# mixer.net
KiCad netlist of a schematic drawn in Altium Designer
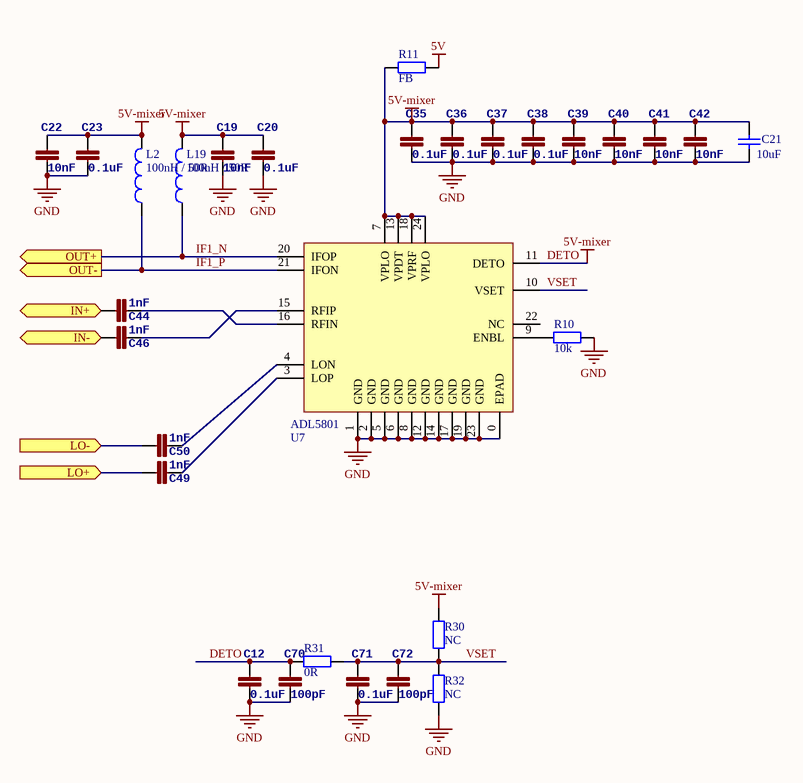
[diagram p0: mixer.SchDoc]

(export (version "E")
  (design (tool "Eeschema 10.0.6"))
  (components
    (comp (ref "C12")
      (value "0.1uF")
      (footprint "0402")
      (description "<b>Capacitor</b>\nStandard 0603 ceramic capacitor, and 0.1\" leaded capacitor.")
      (fields (field (name "PARTNO") "CC0402ZRY5V7BB104"))
      (libsource (lib "*") (part "CAP0402-CAP"))
    )
    (comp (ref "C19")
      (value "10nF")
      (footprint "0402")
      (description "<b>Capacitor</b>\nStandard 0603 ceramic capacitor, and 0.1\" leaded capacitor.")
      (fields (field (name "PARTNO") "CC0402ZRY5V7BB104"))
      (libsource (lib "*") (part "CAP0402-CAP"))
    )
    (comp (ref "C20")
      (value "0.1uF")
      (footprint "0402")
      (description "<b>Capacitor</b>\nStandard 0603 ceramic capacitor, and 0.1\" leaded capacitor.")
      (fields (field (name "PARTNO") "CC0402ZRY5V7BB104"))
      (libsource (lib "*") (part "CAP0402-CAP"))
    )
    (comp (ref "C21")
      (value "10uF")
      (footprint "0805")
      (description "Capacitor")
      (fields (field (name "PUBLISHER") "Altium Limited"))
      (libsource (lib "RTC6705") (part "Cap"))
    )
    (comp (ref "C22")
      (value "10nF")
      (footprint "0402")
      (description "<b>Capacitor</b>\nStandard 0603 ceramic capacitor, and 0.1\" leaded capacitor.")
      (fields (field (name "PARTNO") "CC0402ZRY5V7BB104"))
      (libsource (lib "*") (part "CAP0402-CAP"))
    )
    (comp (ref "C23")
      (value "0.1uF")
      (footprint "0402")
      (description "<b>Capacitor</b>\nStandard 0603 ceramic capacitor, and 0.1\" leaded capacitor.")
      (fields (field (name "PARTNO") "CC0402ZRY5V7BB104"))
      (libsource (lib "*") (part "CAP0402-CAP"))
    )
    (comp (ref "C35")
      (value "0.1uF")
      (footprint "0402")
      (description "<b>Capacitor</b>\nStandard 0603 ceramic capacitor, and 0.1\" leaded capacitor.")
      (fields (field (name "PARTNO") "CC0402ZRY5V7BB104"))
      (libsource (lib "*") (part "CAP0402-CAP"))
    )
    (comp (ref "C36")
      (value "0.1uF")
      (footprint "0402")
      (description "<b>Capacitor</b>\nStandard 0603 ceramic capacitor, and 0.1\" leaded capacitor.")
      (fields (field (name "PARTNO") "CC0402ZRY5V7BB104"))
      (libsource (lib "*") (part "CAP0402-CAP"))
    )
    (comp (ref "C37")
      (value "0.1uF")
      (footprint "0402")
      (description "<b>Capacitor</b>\nStandard 0603 ceramic capacitor, and 0.1\" leaded capacitor.")
      (fields (field (name "PARTNO") "CC0402ZRY5V7BB104"))
      (libsource (lib "*") (part "CAP0402-CAP"))
    )
    (comp (ref "C38")
      (value "0.1uF")
      (footprint "0402")
      (description "<b>Capacitor</b>\nStandard 0603 ceramic capacitor, and 0.1\" leaded capacitor.")
      (fields (field (name "PARTNO") "CC0402ZRY5V7BB104"))
      (libsource (lib "*") (part "CAP0402-CAP"))
    )
    (comp (ref "C39")
      (value "10nF")
      (footprint "0402")
      (description "<b>Capacitor</b>\nStandard 0603 ceramic capacitor, and 0.1\" leaded capacitor.")
      (fields (field (name "PARTNO") "CC0402ZRY5V7BB104"))
      (libsource (lib "*") (part "CAP0402-CAP"))
    )
    (comp (ref "C40")
      (value "10nF")
      (footprint "0402")
      (description "<b>Capacitor</b>\nStandard 0603 ceramic capacitor, and 0.1\" leaded capacitor.")
      (fields (field (name "PARTNO") "CC0402ZRY5V7BB104"))
      (libsource (lib "*") (part "CAP0402-CAP"))
    )
    (comp (ref "C41")
      (value "10nF")
      (footprint "0402")
      (description "<b>Capacitor</b>\nStandard 0603 ceramic capacitor, and 0.1\" leaded capacitor.")
      (fields (field (name "PARTNO") "CC0402ZRY5V7BB104"))
      (libsource (lib "*") (part "CAP0402-CAP"))
    )
    (comp (ref "C42")
      (value "10nF")
      (footprint "0402")
      (description "<b>Capacitor</b>\nStandard 0603 ceramic capacitor, and 0.1\" leaded capacitor.")
      (fields (field (name "PARTNO") "CC0402ZRY5V7BB104"))
      (libsource (lib "*") (part "CAP0402-CAP"))
    )
    (comp (ref "C44")
      (value "1nF")
      (footprint "0402")
      (description "<b>Capacitor</b>\nStandard 0603 ceramic capacitor, and 0.1\" leaded capacitor.")
      (fields (field (name "PARTNO") "CC0402ZRY5V7BB104"))
      (libsource (lib "") (part "CAP0402-CAP_1"))
    )
    (comp (ref "C46")
      (value "1nF")
      (footprint "0402")
      (description "<b>Capacitor</b>\nStandard 0603 ceramic capacitor, and 0.1\" leaded capacitor.")
      (fields (field (name "PARTNO") "CC0402ZRY5V7BB104"))
      (libsource (lib "") (part "CAP0402-CAP_1"))
    )
    (comp (ref "C49")
      (value "1nF")
      (footprint "0402")
      (description "<b>Capacitor</b>\nStandard 0603 ceramic capacitor, and 0.1\" leaded capacitor.")
      (fields (field (name "PARTNO") "CC0402ZRY5V7BB104"))
      (libsource (lib "") (part "CAP0402-CAP_1"))
    )
    (comp (ref "C50")
      (value "1nF")
      (footprint "0402")
      (description "<b>Capacitor</b>\nStandard 0603 ceramic capacitor, and 0.1\" leaded capacitor.")
      (fields (field (name "PARTNO") "CC0402ZRY5V7BB104"))
      (libsource (lib "") (part "CAP0402-CAP_1"))
    )
    (comp (ref "C70")
      (value "100pF")
      (footprint "0402")
      (description "<b>Capacitor</b>\nStandard 0603 ceramic capacitor, and 0.1\" leaded capacitor.")
      (fields (field (name "PARTNO") "CC0402ZRY5V7BB104"))
      (libsource (lib "*") (part "CAP0402-CAP"))
    )
    (comp (ref "C71")
      (value "0.1uF")
      (footprint "0402")
      (description "<b>Capacitor</b>\nStandard 0603 ceramic capacitor, and 0.1\" leaded capacitor.")
      (fields (field (name "PARTNO") "CC0402ZRY5V7BB104"))
      (libsource (lib "*") (part "CAP0402-CAP"))
    )
    (comp (ref "C72")
      (value "100pF")
      (footprint "0402")
      (description "<b>Capacitor</b>\nStandard 0603 ceramic capacitor, and 0.1\" leaded capacitor.")
      (fields (field (name "PARTNO") "CC0402ZRY5V7BB104"))
      (libsource (lib "*") (part "CAP0402-CAP"))
    )
    (comp (ref "L2")
      (value "100nH / 50R")
      (footprint "0603")
      (description "Inductor")
      (fields (field (name "PUBLISHER") "Altium Limited"))
      (libsource (lib "Miscellaneous Devices") (part "Inductor"))
    )
    (comp (ref "L19")
      (value "100nH / 50R")
      (footprint "0603")
      (description "Inductor")
      (fields (field (name "PUBLISHER") "Altium Limited"))
      (libsource (lib "Miscellaneous Devices") (part "Inductor"))
    )
    (comp (ref "R10")
      (value "10k")
      (footprint "0402")
      (description "Resistor")
      (fields (field (name "Comment") "Res2") (field (name "PUBLISHER") "Altium Limited"))
      (libsource (lib "") (part "Res2_1"))
    )
    (comp (ref "R11")
      (value "FB")
      (footprint "0603")
      (description "Resistor")
      (fields (field (name "PUBLISHER") "Altium Limited"))
      (libsource (lib "Miscellaneous Devices") (part "Res2"))
    )
    (comp (ref "R30")
      (value "NC")
      (footprint "0402")
      (description "Resistor")
      (fields (field (name "Comment") "Res2") (field (name "PUBLISHER") "Altium Limited"))
      (libsource (lib "RTC6705") (part "Res2"))
    )
    (comp (ref "R31")
      (value "0R")
      (footprint "0402")
      (description "Resistor")
      (fields (field (name "Comment") "Res2") (field (name "PUBLISHER") "Altium Limited"))
      (libsource (lib "") (part "Res2_1"))
    )
    (comp (ref "R32")
      (value "NC")
      (footprint "0402")
      (description "Resistor")
      (fields (field (name "Comment") "Res2") (field (name "PUBLISHER") "Altium Limited"))
      (libsource (lib "RTC6705") (part "Res2"))
    )
    (comp (ref "U7") (value "ADL5801") (footprint "ADL5801") (libsource (lib "F4SDR") (part "ADL5801")))
  )
  (nets
    (net (code "1") (name "/IF1_N") (class "Default")
      (node (ref "L19") (pin "1") (pinfunction "1_1") (pintype "passive"))
      (node (ref "U7") (pin "20") (pinfunction "IFOP_20") (pintype "passive"))
    )
    (net (code "2") (name "/IF1_P") (class "Default")
      (node (ref "L2") (pin "1") (pinfunction "1_1") (pintype "passive"))
      (node (ref "U7") (pin "21") (pinfunction "IFON_21") (pintype "passive"))
    )
    (net (code "3") (name "/IN+") (class "Default")
      (node (ref "C44") (pin "1") (pinfunction "1_1") (pintype "passive"))
    )
    (net (code "4") (name "/IN-") (class "Default")
      (node (ref "C46") (pin "1") (pinfunction "1_1") (pintype "passive"))
    )
    (net (code "5") (name "/LO+") (class "Default")
      (node (ref "C49") (pin "1") (pinfunction "1_1") (pintype "passive"))
    )
    (net (code "6") (name "/LO-") (class "Default")
      (node (ref "C50") (pin "1") (pinfunction "1_1") (pintype "passive"))
    )
    (net (code "7") (name "/VSET") (class "Default")
      (node (ref "C71") (pin "2") (pinfunction "2_2") (pintype "passive"))
      (node (ref "C72") (pin "2") (pinfunction "2_2") (pintype "passive"))
      (node (ref "R30") (pin "1") (pinfunction "1_1") (pintype "passive"))
      (node (ref "R31") (pin "2") (pinfunction "2_2") (pintype "passive"))
      (node (ref "R32") (pin "2") (pinfunction "2_2") (pintype "passive"))
      (node (ref "U7") (pin "10") (pinfunction "VSET_10") (pintype "passive"))
    )
    (net (code "8") (name "5V") (class "Default")
      (node (ref "R11") (pin "2") (pinfunction "2_2") (pintype "passive"))
    )
    (net (code "9") (name "5V-mixer") (class "Default")
      (node (ref "C12") (pin "2") (pinfunction "2_2") (pintype "passive"))
      (node (ref "C19") (pin "2") (pinfunction "2_2") (pintype "passive"))
      (node (ref "C20") (pin "2") (pinfunction "2_2") (pintype "passive"))
      (node (ref "C21") (pin "2") (pinfunction "2_2") (pintype "passive"))
      (node (ref "C22") (pin "2") (pinfunction "2_2") (pintype "passive"))
      (node (ref "C23") (pin "2") (pinfunction "2_2") (pintype "passive"))
      (node (ref "C35") (pin "2") (pinfunction "2_2") (pintype "passive"))
      (node (ref "C36") (pin "2") (pinfunction "2_2") (pintype "passive"))
      (node (ref "C37") (pin "2") (pinfunction "2_2") (pintype "passive"))
      (node (ref "C38") (pin "2") (pinfunction "2_2") (pintype "passive"))
      (node (ref "C39") (pin "2") (pinfunction "2_2") (pintype "passive"))
      (node (ref "C40") (pin "2") (pinfunction "2_2") (pintype "passive"))
      (node (ref "C41") (pin "2") (pinfunction "2_2") (pintype "passive"))
      (node (ref "C42") (pin "2") (pinfunction "2_2") (pintype "passive"))
      (node (ref "C70") (pin "2") (pinfunction "2_2") (pintype "passive"))
      (node (ref "L19") (pin "2") (pinfunction "2_2") (pintype "passive"))
      (node (ref "L2") (pin "2") (pinfunction "2_2") (pintype "passive"))
      (node (ref "R11") (pin "1") (pinfunction "1_1") (pintype "passive"))
      (node (ref "R30") (pin "2") (pinfunction "2_2") (pintype "passive"))
      (node (ref "R31") (pin "1") (pinfunction "1_1") (pintype "passive"))
      (node (ref "U7") (pin "11") (pinfunction "DETO_11") (pintype "passive"))
      (node (ref "U7") (pin "13") (pinfunction "VPDT_13") (pintype "passive"))
      (node (ref "U7") (pin "18") (pinfunction "VPRF_18") (pintype "passive"))
      (node (ref "U7") (pin "24") (pinfunction "VPLO_24") (pintype "passive"))
      (node (ref "U7") (pin "7") (pinfunction "VPLO_7") (pintype "passive"))
    )
    (net (code "10") (name "GND") (class "Default")
      (node (ref "C12") (pin "1") (pinfunction "1_1") (pintype "passive"))
      (node (ref "C19") (pin "1") (pinfunction "1_1") (pintype "passive"))
      (node (ref "C20") (pin "1") (pinfunction "1_1") (pintype "passive"))
      (node (ref "C21") (pin "1") (pinfunction "1_1") (pintype "passive"))
      (node (ref "C22") (pin "1") (pinfunction "1_1") (pintype "passive"))
      (node (ref "C23") (pin "1") (pinfunction "1_1") (pintype "passive"))
      (node (ref "C35") (pin "1") (pinfunction "1_1") (pintype "passive"))
      (node (ref "C36") (pin "1") (pinfunction "1_1") (pintype "passive"))
      (node (ref "C37") (pin "1") (pinfunction "1_1") (pintype "passive"))
      (node (ref "C38") (pin "1") (pinfunction "1_1") (pintype "passive"))
      (node (ref "C39") (pin "1") (pinfunction "1_1") (pintype "passive"))
      (node (ref "C40") (pin "1") (pinfunction "1_1") (pintype "passive"))
      (node (ref "C41") (pin "1") (pinfunction "1_1") (pintype "passive"))
      (node (ref "C42") (pin "1") (pinfunction "1_1") (pintype "passive"))
      (node (ref "C70") (pin "1") (pinfunction "1_1") (pintype "passive"))
      (node (ref "C71") (pin "1") (pinfunction "1_1") (pintype "passive"))
      (node (ref "C72") (pin "1") (pinfunction "1_1") (pintype "passive"))
      (node (ref "R10") (pin "2") (pinfunction "2_2") (pintype "passive"))
      (node (ref "R32") (pin "1") (pinfunction "1_1") (pintype "passive"))
      (node (ref "U7") (pin "0") (pinfunction "EPAD_0") (pintype "passive"))
      (node (ref "U7") (pin "1") (pinfunction "GND_1") (pintype "passive"))
      (node (ref "U7") (pin "12") (pinfunction "GND_12") (pintype "passive"))
      (node (ref "U7") (pin "14") (pinfunction "GND_14") (pintype "passive"))
      (node (ref "U7") (pin "17") (pinfunction "GND_17") (pintype "passive"))
      (node (ref "U7") (pin "19") (pinfunction "GND_19") (pintype "passive"))
      (node (ref "U7") (pin "2") (pinfunction "GND_2") (pintype "passive"))
      (node (ref "U7") (pin "23") (pinfunction "GND_23") (pintype "passive"))
      (node (ref "U7") (pin "5") (pinfunction "GND_5") (pintype "passive"))
      (node (ref "U7") (pin "6") (pinfunction "GND_6") (pintype "passive"))
      (node (ref "U7") (pin "8") (pinfunction "GND_8") (pintype "passive"))
    )
    (net (code "11") (name "Net-(U7-ENBL)") (class "Default")
      (node (ref "R10") (pin "1") (pinfunction "1_1") (pintype "passive"))
      (node (ref "U7") (pin "9") (pinfunction "ENBL_9") (pintype "passive"))
    )
    (net (code "12") (name "Net-(U7-LON)") (class "Default")
      (node (ref "C50") (pin "2") (pinfunction "2_2") (pintype "passive"))
      (node (ref "U7") (pin "4") (pinfunction "LON_4") (pintype "passive"))
    )
    (net (code "13") (name "Net-(U7-LOP)") (class "Default")
      (node (ref "C49") (pin "2") (pinfunction "2_2") (pintype "passive"))
      (node (ref "U7") (pin "3") (pinfunction "LOP_3") (pintype "passive"))
    )
    (net (code "14") (name "Net-(U7-RFIN)") (class "Default")
      (node (ref "C44") (pin "2") (pinfunction "2_2") (pintype "passive"))
      (node (ref "U7") (pin "16") (pinfunction "RFIN_16") (pintype "passive"))
    )
    (net (code "15") (name "Net-(U7-RFIP)") (class "Default")
      (node (ref "C46") (pin "2") (pinfunction "2_2") (pintype "passive"))
      (node (ref "U7") (pin "15") (pinfunction "RFIP_15") (pintype "passive"))
    )
    (net (code "16") (name "unconnected-(U7-NC-Pad22)") (class "Default")
      (node (ref "U7") (pin "22") (pinfunction "NC_22") (pintype "passive"))
    )
  )
)
